# POWER.net
KiCad netlist of a schematic drawn in Altium Designer
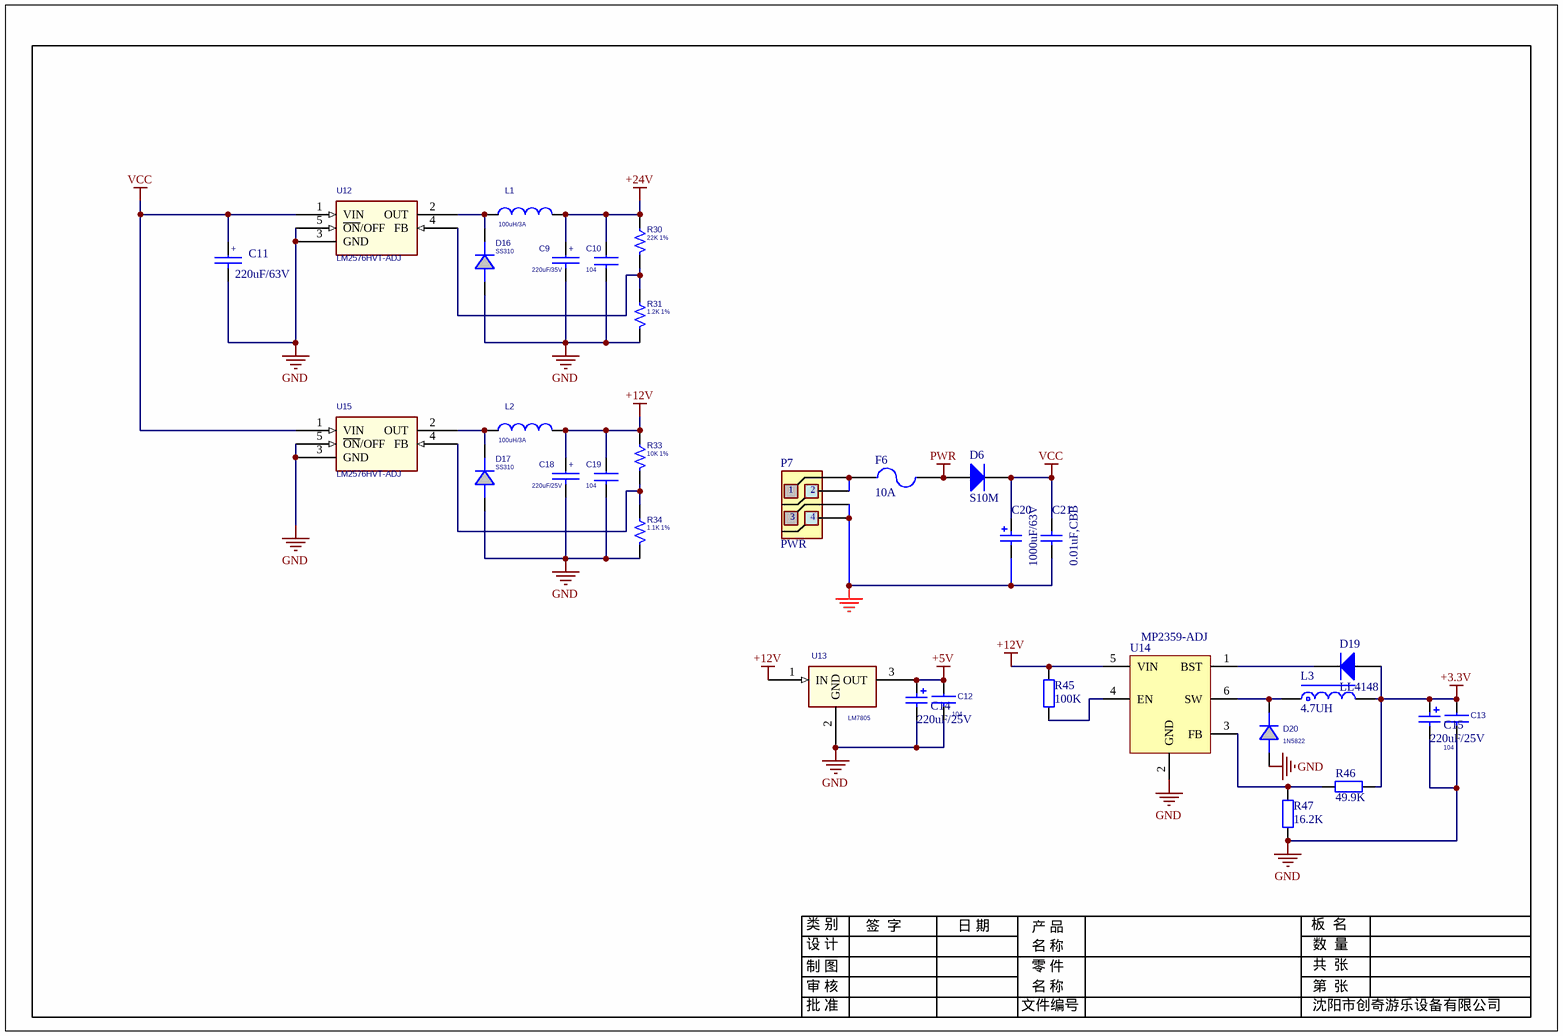
[diagram p0: POWER.SchDoc]

(export (version "E")
  (design (tool "Eeschema 10.0.6"))
  (components
    (comp (ref "C9")
      (value "220uF/35V")
      (footprint "CAP 3.5*8*11.5")
      (description "100uF/16V,100uF/35V")
      (libsource (lib "PCB_Project") (part "CAP POL_3"))
    )
    (comp (ref "C10") (value "104") (footprint "C 0805") (libsource (lib "PCB_Project") (part "CAP NP")))
    (comp (ref "C11")
      (value "220uF/63V")
      (footprint "CAP 5.0*10*16")
      (description "220uF/63V,470uF/50V")
      (libsource (lib "PCB_Project") (part "CAP POL_4_1"))
    )
    (comp (ref "C12") (value "104") (footprint "C 0805") (libsource (lib "*") (part "CAP NP")))
    (comp (ref "C13") (value "104") (footprint "C 0805") (libsource (lib "*") (part "CAP NP")))
    (comp (ref "C14")
      (value "220uF/25V")
      (footprint "CAP 2.5*6.3*11.2 - BK")
      (description "Polarized Capacitor (Axial)")
      (fields (field (name "PUBLISHER") "Altium Limited"))
      (libsource (lib "Miscellaneous Devices") (part "Cap Pol2"))
    )
    (comp (ref "C15")
      (value "220uF/25V")
      (footprint "CAP 2.5*6.3*11.2 - BK")
      (description "Polarized Capacitor (Axial)")
      (fields (field (name "PUBLISHER") "Altium Limited"))
      (libsource (lib "Miscellaneous Devices") (part "Cap Pol2"))
    )
    (comp (ref "C18")
      (value "220uF/25V")
      (footprint "CAP 2.5*6.3*7")
      (description "100uF/16V,100uF/35V")
      (libsource (lib "PCB_Project") (part "CAP POL_3"))
    )
    (comp (ref "C19") (value "104") (footprint "C 0805") (libsource (lib "PCB_Project") (part "CAP NP")))
    (comp (ref "C20")
      (value "1000uF/63V")
      (footprint "CAP 7.5*16*25")
      (description "Polarized Capacitor (Axial)")
      (fields (field (name "PUBLISHER") "Altium Limited"))
      (libsource (lib "Miscellaneous Devices") (part "Cap Pol2"))
    )
    (comp (ref "C21")
      (value "0.01uF,CBB")
      (footprint "MLCC5.08-A")
      (description "Capacitor")
      (fields (field (name "PUBLISHER") "Altium Limited"))
      (libsource (lib "Miscellaneous Devices") (part "Cap"))
    )
    (comp (ref "D6") (value "S10M") (footprint "SMC") (libsource (lib "any") (part "Diode")))
    (comp (ref "D16") (value "SS310") (footprint "SMC") (libsource (lib "PCB_Project") (part "DIODE_1")))
    (comp (ref "D17") (value "SS310") (footprint "SMC") (libsource (lib "PCB_Project") (part "DIODE_1")))
    (comp (ref "D19") (value "LL4148") (footprint "MINI_MELF (LL34)") (libsource (lib "any") (part "Diode")))
    (comp (ref "D20") (value "1N5822") (footprint "SMA") (libsource (lib "*") (part "DIODE")))
    (comp (ref "F6")
      (value "10A")
      (footprint "FUSEe-CAR")
      (description "Fuse")
      (fields (field (name "PUBLISHER") "Altium Limited"))
      (libsource (lib "any") (part "Fuse 2"))
    )
    (comp (ref "L1")
      (value "100uH/3A")
      (footprint "PK1618")
      (libsource (lib "PCB_Project") (part "INDUCTOR_2"))
    )
    (comp (ref "L2")
      (value "100uH/3A")
      (footprint "PK1618")
      (libsource (lib "PCB_Project") (part "INDUCTOR_2"))
    )
    (comp (ref "L3")
      (value "4.7UH")
      (footprint "CD31")
      (description "贴片功率电感")
      (fields (field (name "版权归属") "源创客"))
      (libsource (lib "电阻-电容-电感") (part "L-CD"))
    )
    (comp (ref "P7") (value "PWR") (footprint "557-2x2") (libsource (lib "*") (part "CON4L")))
    (comp (ref "R30")
      (value "22K 1%")
      (footprint "R 0805")
      (libsource (lib "PCB_Project") (part "RESISTOR 1"))
    )
    (comp (ref "R31")
      (value "1.2K 1%")
      (footprint "R 0805")
      (libsource (lib "PCB_Project") (part "RESISTOR 1"))
    )
    (comp (ref "R33")
      (value "10K 1%")
      (footprint "R 0805")
      (libsource (lib "PCB_Project") (part "RESISTOR 1"))
    )
    (comp (ref "R34")
      (value "1.1K 1%")
      (footprint "R 0805")
      (libsource (lib "PCB_Project") (part "RESISTOR 1"))
    )
    (comp (ref "R45")
      (value "100K")
      (footprint "R 0805")
      (libsource (lib "YXF_ComponentLibrary") (part "Res1"))
    )
    (comp (ref "R46") (value "49.9K") (footprint "R 0805") (libsource (lib "") (part "Res1_1")))
    (comp (ref "R47")
      (value "16.2K")
      (footprint "R 0805")
      (libsource (lib "YXF_ComponentLibrary") (part "Res1"))
    )
    (comp (ref "U12")
      (value "LM2576HVT-ADJ")
      (footprint "TO220-5")
      (libsource (lib "PCB_Project") (part "LM2576HVT-ADJ"))
    )
    (comp (ref "U13") (value "LM7805") (footprint "TO220A") (libsource (lib "*") (part "LM7805")))
    (comp (ref "U14")
      (value "MP2359-ADJ")
      (footprint "SOT23-6L")
      (description "输入：4.5V-24V  输出：0-15V 1.2A")
      (libsource (lib "Power") (part "MP2359"))
    )
    (comp (ref "U15")
      (value "LM2576HVT-ADJ")
      (footprint "TO220-5")
      (libsource (lib "PCB_Project") (part "LM2576HVT-ADJ"))
    )
  )
  (nets
    (net (code "1") (name "+3.3V") (class "Default")
      (node (ref "C13") (pin "1") (pinfunction "1_1") (pintype "passive"))
      (node (ref "C15") (pin "1") (pinfunction "1_1") (pintype "passive"))
      (node (ref "D19") (pin "1") (pinfunction "1_1") (pintype "passive"))
      (node (ref "L3") (pin "2") (pinfunction "2_2") (pintype "passive"))
      (node (ref "R46") (pin "2") (pinfunction "2_2") (pintype "passive"))
    )
    (net (code "2") (name "+5V") (class "Default")
      (node (ref "C12") (pin "1") (pinfunction "1_1") (pintype "passive"))
      (node (ref "C14") (pin "1") (pinfunction "1_1") (pintype "passive"))
      (node (ref "U13") (pin "3") (pinfunction "OUT_3") (pintype "passive"))
    )
    (net (code "3") (name "+12V") (class "Default")
      (node (ref "C18") (pin "1") (pinfunction "1_1") (pintype "passive"))
      (node (ref "C19") (pin "1") (pinfunction "1_1") (pintype "passive"))
      (node (ref "L2") (pin "2") (pinfunction "2_2") (pintype "passive"))
      (node (ref "R33") (pin "1") (pinfunction "1_1") (pintype "passive"))
      (node (ref "R45") (pin "1") (pinfunction "1_1") (pintype "passive"))
      (node (ref "U13") (pin "1") (pinfunction "IN_1") (pintype "input"))
      (node (ref "U14") (pin "5") (pinfunction "VIN_5") (pintype "passive"))
    )
    (net (code "4") (name "+24V") (class "Default")
      (node (ref "C10") (pin "1") (pinfunction "1_1") (pintype "passive"))
      (node (ref "C9") (pin "1") (pinfunction "1_1") (pintype "passive"))
      (node (ref "L1") (pin "2") (pinfunction "2_2") (pintype "passive"))
      (node (ref "R30") (pin "1") (pinfunction "1_1") (pintype "passive"))
    )
    (net (code "5") (name "GND") (class "Default")
      (node (ref "C10") (pin "2") (pinfunction "2_2") (pintype "passive"))
      (node (ref "C11") (pin "2") (pinfunction "2_2") (pintype "passive"))
      (node (ref "C12") (pin "2") (pinfunction "2_2") (pintype "passive"))
      (node (ref "C13") (pin "2") (pinfunction "2_2") (pintype "passive"))
      (node (ref "C14") (pin "2") (pinfunction "2_2") (pintype "passive"))
      (node (ref "C15") (pin "2") (pinfunction "2_2") (pintype "passive"))
      (node (ref "C18") (pin "2") (pinfunction "2_2") (pintype "passive"))
      (node (ref "C19") (pin "2") (pinfunction "2_2") (pintype "passive"))
      (node (ref "C20") (pin "2") (pinfunction "2_2") (pintype "passive"))
      (node (ref "C21") (pin "1") (pinfunction "1_1") (pintype "passive"))
      (node (ref "C9") (pin "2") (pinfunction "2_2") (pintype "passive"))
      (node (ref "D16") (pin "1") (pinfunction "ANODE_1") (pintype "passive"))
      (node (ref "D17") (pin "1") (pinfunction "ANODE_1") (pintype "passive"))
      (node (ref "D20") (pin "1") (pinfunction "ANODE_1") (pintype "passive"))
      (node (ref "P7") (pin "3") (pinfunction "3_3") (pintype "passive"))
      (node (ref "P7") (pin "4") (pinfunction "4_4") (pintype "passive"))
      (node (ref "R31") (pin "2") (pinfunction "2_2") (pintype "passive"))
      (node (ref "R34") (pin "2") (pinfunction "2_2") (pintype "passive"))
      (node (ref "R47") (pin "2") (pinfunction "2_2") (pintype "passive"))
      (node (ref "U12") (pin "3") (pinfunction "GND_3") (pintype "power_in"))
      (node (ref "U12") (pin "5") (pinfunction "~{ON}/OFF_5") (pintype "input"))
      (node (ref "U13") (pin "2") (pinfunction "GND_2") (pintype "power_in"))
      (node (ref "U14") (pin "2") (pinfunction "GND_2") (pintype "passive"))
      (node (ref "U15") (pin "3") (pinfunction "GND_3") (pintype "power_in"))
      (node (ref "U15") (pin "5") (pinfunction "~{ON}/OFF_5") (pintype "input"))
    )
    (net (code "6") (name "Net-(D16-CATHODE)") (class "Default")
      (node (ref "D16") (pin "2") (pinfunction "CATHODE_2") (pintype "passive"))
      (node (ref "L1") (pin "1") (pinfunction "1_1") (pintype "passive"))
      (node (ref "U12") (pin "2") (pinfunction "OUT_2") (pintype "open_emitter"))
    )
    (net (code "7") (name "Net-(D17-CATHODE)") (class "Default")
      (node (ref "D17") (pin "2") (pinfunction "CATHODE_2") (pintype "passive"))
      (node (ref "L2") (pin "1") (pinfunction "1_1") (pintype "passive"))
      (node (ref "U15") (pin "2") (pinfunction "OUT_2") (pintype "open_emitter"))
    )
    (net (code "8") (name "Net-(D20-CATHODE)") (class "Default")
      (node (ref "D20") (pin "2") (pinfunction "CATHODE_2") (pintype "passive"))
      (node (ref "L3") (pin "1") (pinfunction "1_1") (pintype "passive"))
      (node (ref "U14") (pin "6") (pinfunction "SW_6") (pintype "power_in"))
    )
    (net (code "9") (name "Net-(F6-Pad2)") (class "Default")
      (node (ref "F6") (pin "2") (pinfunction "2_2") (pintype "passive"))
      (node (ref "P7") (pin "1") (pinfunction "1_1") (pintype "passive"))
      (node (ref "P7") (pin "2") (pinfunction "2_2") (pintype "passive"))
    )
    (net (code "10") (name "Net-(U12-FB)") (class "Default")
      (node (ref "R30") (pin "2") (pinfunction "2_2") (pintype "passive"))
      (node (ref "R31") (pin "1") (pinfunction "1_1") (pintype "passive"))
      (node (ref "U12") (pin "4") (pinfunction "FB_4") (pintype "input"))
    )
    (net (code "11") (name "Net-(U14-BST)") (class "Default")
      (node (ref "D19") (pin "2") (pinfunction "2_2") (pintype "passive"))
      (node (ref "U14") (pin "1") (pinfunction "BST_1") (pintype "open_emitter"))
    )
    (net (code "12") (name "Net-(U14-EN)") (class "Default")
      (node (ref "R45") (pin "2") (pinfunction "2_2") (pintype "passive"))
      (node (ref "U14") (pin "4") (pinfunction "EN_4") (pintype "power_in"))
    )
    (net (code "13") (name "Net-(U14-FB)") (class "Default")
      (node (ref "R46") (pin "1") (pinfunction "1_1") (pintype "passive"))
      (node (ref "R47") (pin "1") (pinfunction "1_1") (pintype "passive"))
      (node (ref "U14") (pin "3") (pinfunction "FB_3") (pintype "passive"))
    )
    (net (code "14") (name "Net-(U15-FB)") (class "Default")
      (node (ref "R33") (pin "2") (pinfunction "2_2") (pintype "passive"))
      (node (ref "R34") (pin "1") (pinfunction "1_1") (pintype "passive"))
      (node (ref "U15") (pin "4") (pinfunction "FB_4") (pintype "input"))
    )
    (net (code "15") (name "PWR") (class "Default")
      (node (ref "D6") (pin "1") (pinfunction "1_1") (pintype "passive"))
      (node (ref "F6") (pin "1") (pinfunction "1_1") (pintype "passive"))
    )
    (net (code "16") (name "VCC") (class "Default")
      (node (ref "C11") (pin "1") (pinfunction "1_1") (pintype "passive"))
      (node (ref "C20") (pin "1") (pinfunction "1_1") (pintype "passive"))
      (node (ref "C21") (pin "2") (pinfunction "2_2") (pintype "passive"))
      (node (ref "D6") (pin "2") (pinfunction "2_2") (pintype "passive"))
      (node (ref "U12") (pin "1") (pinfunction "VIN_1") (pintype "input"))
      (node (ref "U15") (pin "1") (pinfunction "VIN_1") (pintype "input"))
    )
  )
)
